# uc.net
KiCad netlist of a schematic drawn in Altium Designer
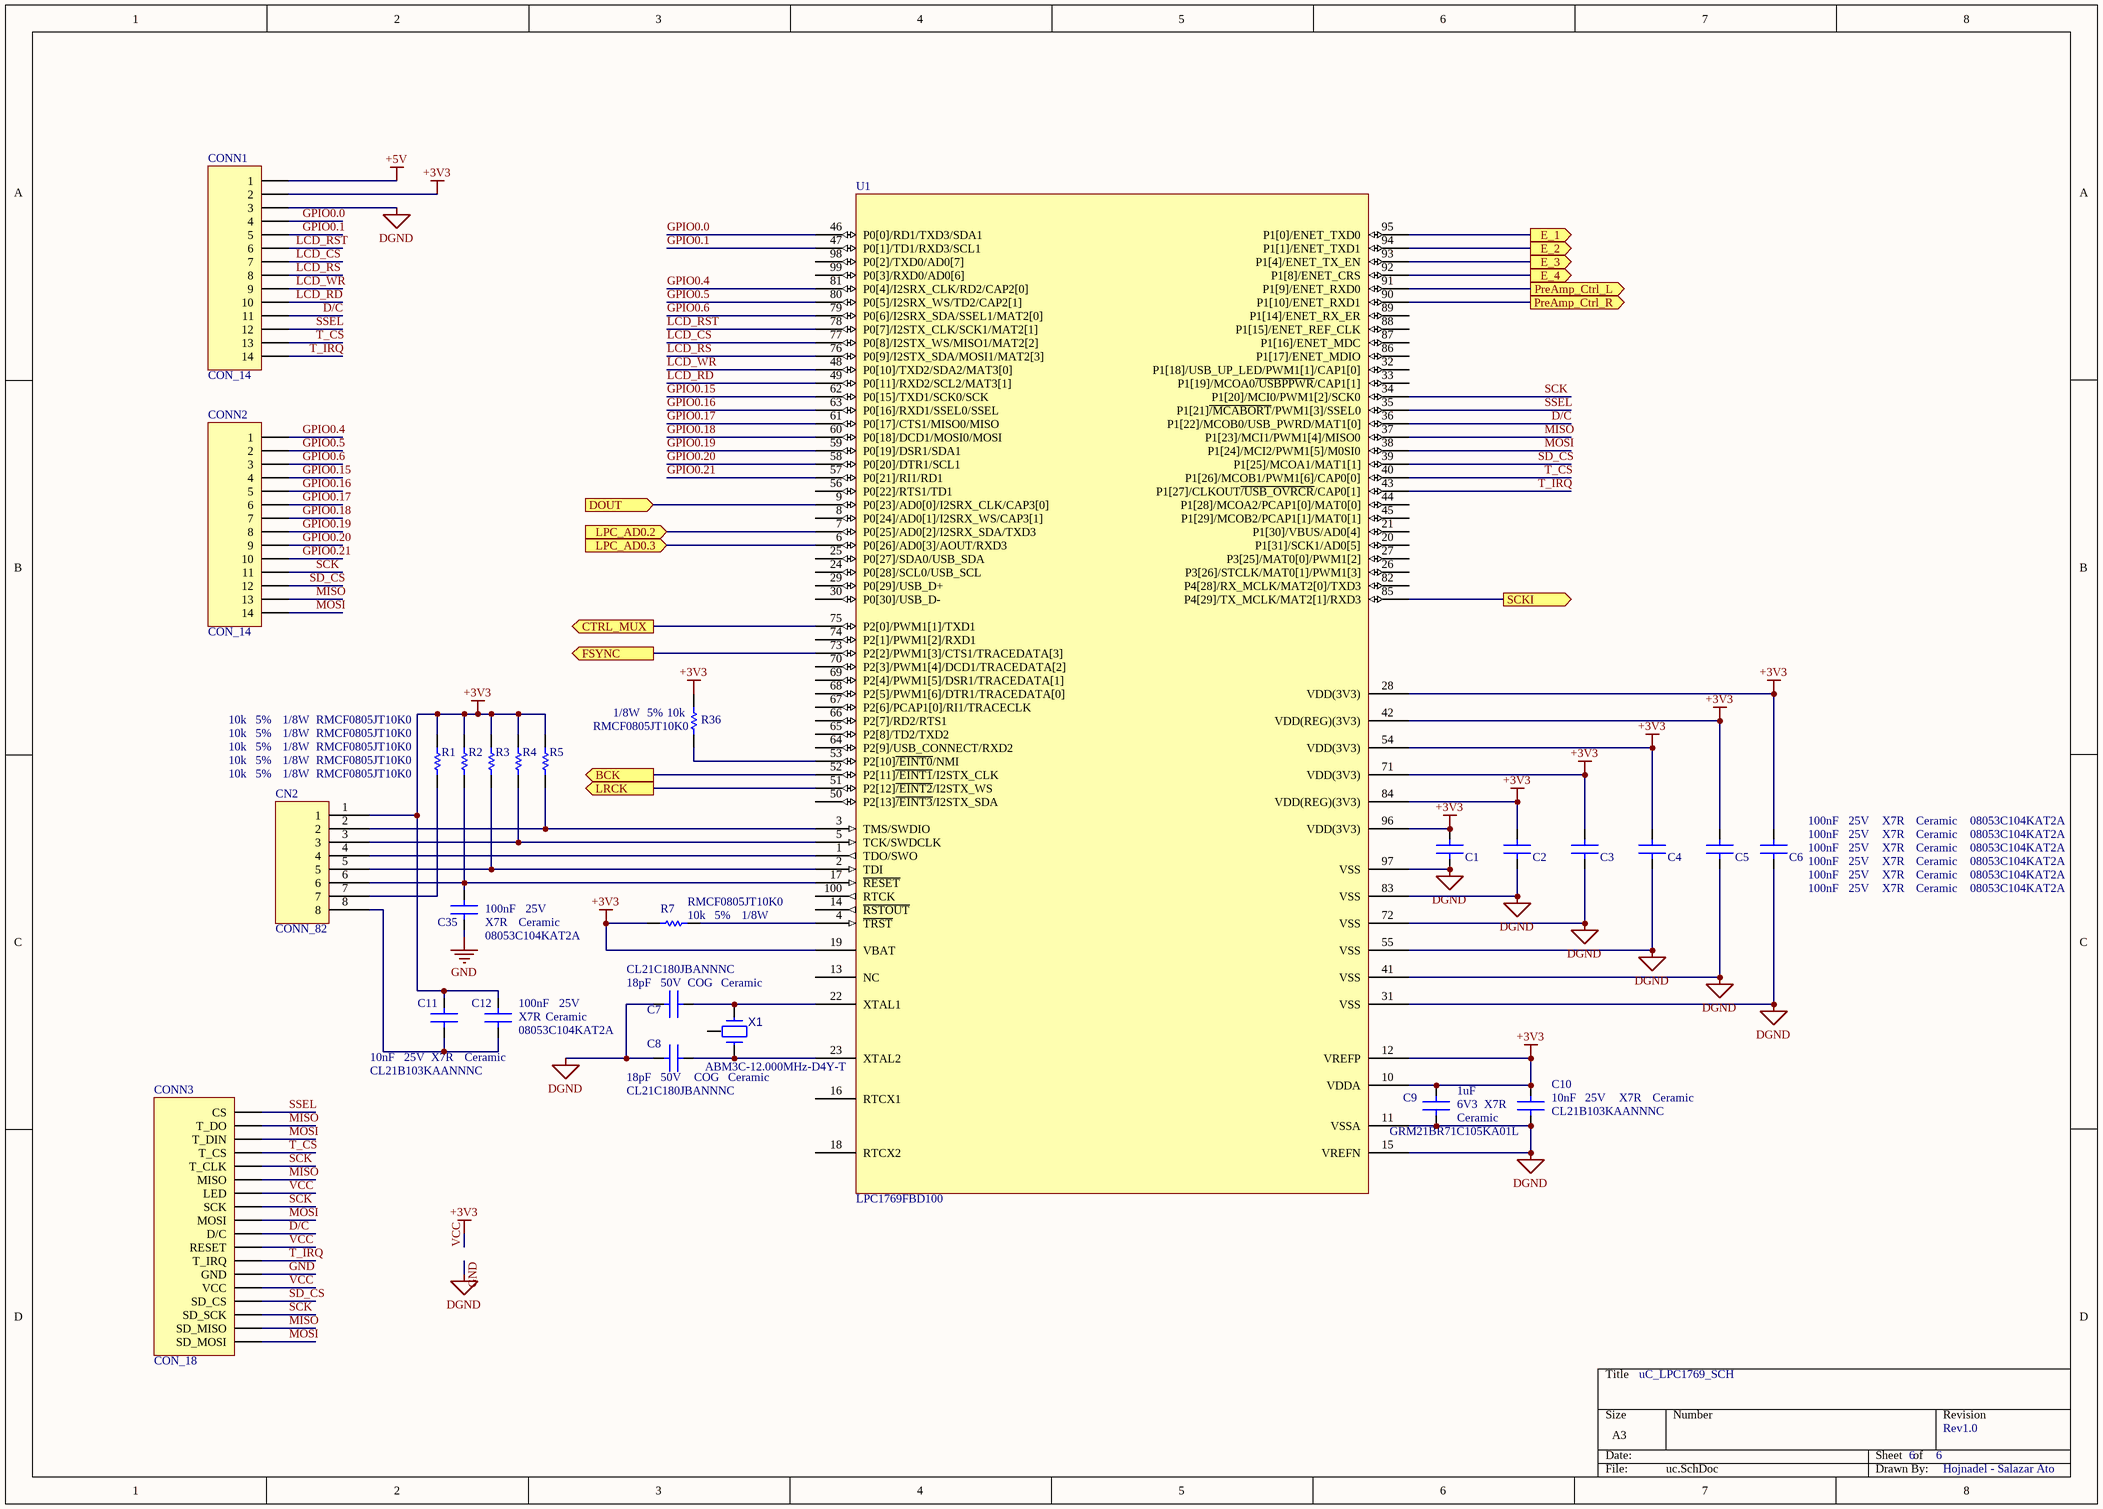
[diagram p0: uc.SchDoc]

(export (version "E")
  (design (tool "Eeschema 10.0.6"))
  (components
    (comp (ref "C1")
      (value "100nF 25V X7R Ceramic")
      (footprint "C_0805")
      (description "Capacitor")
      (fields
        (field (name "C") "100nF")
        (field (name "V") "25V")
        (field (name "PART NUMBER") "08053C104KAT2A")
        (field (name "TEMP COEF") "X7R")
        (field (name "MATERIAL") "Ceramic")
      )
      (libsource (lib "TDII_Lib_V2") (part "Cap1"))
    )
    (comp (ref "C2")
      (value "100nF 25V X7R Ceramic")
      (footprint "C_0805")
      (description "Capacitor")
      (fields
        (field (name "C") "100nF")
        (field (name "V") "25V")
        (field (name "PART NUMBER") "08053C104KAT2A")
        (field (name "TEMP COEF") "X7R")
        (field (name "MATERIAL") "Ceramic")
      )
      (libsource (lib "TDII_Lib_V2") (part "Cap1"))
    )
    (comp (ref "C3")
      (value "100nF 25V X7R Ceramic")
      (footprint "C_0805")
      (description "Capacitor")
      (fields
        (field (name "C") "100nF")
        (field (name "V") "25V")
        (field (name "PART NUMBER") "08053C104KAT2A")
        (field (name "TEMP COEF") "X7R")
        (field (name "MATERIAL") "Ceramic")
      )
      (libsource (lib "TDII_Lib_V2") (part "Cap1"))
    )
    (comp (ref "C4")
      (value "100nF 25V X7R Ceramic")
      (footprint "C_0805")
      (description "Capacitor")
      (fields
        (field (name "C") "100nF")
        (field (name "V") "25V")
        (field (name "PART NUMBER") "08053C104KAT2A")
        (field (name "TEMP COEF") "X7R")
        (field (name "MATERIAL") "Ceramic")
      )
      (libsource (lib "TDII_Lib_V2") (part "Cap1"))
    )
    (comp (ref "C5")
      (value "100nF 25V X7R Ceramic")
      (footprint "C_0805")
      (description "Capacitor")
      (fields
        (field (name "C") "100nF")
        (field (name "V") "25V")
        (field (name "PART NUMBER") "08053C104KAT2A")
        (field (name "TEMP COEF") "X7R")
        (field (name "MATERIAL") "Ceramic")
      )
      (libsource (lib "TDII_Lib_V2") (part "Cap1"))
    )
    (comp (ref "C6")
      (value "100nF 25V X7R Ceramic")
      (footprint "C_0805")
      (description "Capacitor")
      (fields
        (field (name "C") "100nF")
        (field (name "V") "25V")
        (field (name "PART NUMBER") "08053C104KAT2A")
        (field (name "TEMP COEF") "X7R")
        (field (name "MATERIAL") "Ceramic")
      )
      (libsource (lib "TDII_Lib_V2") (part "Cap1"))
    )
    (comp (ref "C7")
      (value "18pF 50V COG Ceramic")
      (footprint "C_0805")
      (description "Capacitor")
      (fields
        (field (name "C") "18pF")
        (field (name "V") "50V")
        (field (name "PART NUMBER") "CL21C180JBANNNC")
        (field (name "TEMP COEF") "COG")
        (field (name "MATERIAL") "Ceramic")
      )
      (libsource (lib "TDII_Lib_V2") (part "Cap1"))
    )
    (comp (ref "C8")
      (value "18pF 50V COG Ceramic")
      (footprint "C_0805")
      (description "Capacitor")
      (fields
        (field (name "C") "18pF")
        (field (name "V") "50V")
        (field (name "PART NUMBER") "CL21C180JBANNNC")
        (field (name "TEMP COEF") "COG")
        (field (name "MATERIAL") "Ceramic")
      )
      (libsource (lib "TDII_Lib_V2") (part "Cap1"))
    )
    (comp (ref "C9")
      (value "1uF 6V3 X7R Ceramic")
      (footprint "C_0805")
      (description "Capacitor")
      (fields
        (field (name "C") "1uF")
        (field (name "V") "6V3")
        (field (name "PART NUMBER") "GRM21BR71C105KA01L")
        (field (name "TEMP COEF") "X7R")
        (field (name "MATERIAL") "Ceramic")
      )
      (libsource (lib "TDII_Lib_V2") (part "Cap1"))
    )
    (comp (ref "C10")
      (value "10nF 25V X7R Ceramic")
      (footprint "C_0805")
      (description "Capacitor")
      (fields
        (field (name "C") "10nF")
        (field (name "V") "25V")
        (field (name "PART NUMBER") "CL21B103KAANNNC")
        (field (name "TEMP COEF") "X7R")
        (field (name "MATERIAL") "Ceramic")
      )
      (libsource (lib "TDII_Lib_V2") (part "Cap1"))
    )
    (comp (ref "C11")
      (value "10nF 25V X7R Ceramic")
      (footprint "C_0805")
      (description "Capacitor")
      (fields
        (field (name "C") "10nF")
        (field (name "V") "25V")
        (field (name "PART NUMBER") "CL21B103KAANNNC")
        (field (name "TEMP COEF") "X7R")
        (field (name "MATERIAL") "Ceramic")
      )
      (libsource (lib "TDII_Lib_V2") (part "Cap1"))
    )
    (comp (ref "C12")
      (value "100nF 25V X7R Ceramic")
      (footprint "C_0805")
      (description "Capacitor")
      (fields
        (field (name "C") "100nF")
        (field (name "V") "25V")
        (field (name "PART NUMBER") "08053C104KAT2A")
        (field (name "TEMP COEF") "X7R")
        (field (name "MATERIAL") "Ceramic")
      )
      (libsource (lib "TDII_Lib_V2") (part "C?"))
    )
    (comp (ref "C35")
      (value "100nF 25V X7R Ceramic")
      (footprint "C_0805")
      (description "Capacitor")
      (fields
        (field (name "C") "100nF")
        (field (name "V") "25V")
        (field (name "TEMP COEF") "X7R")
        (field (name "PART NUMBER") "08053C104KAT2A")
        (field (name "MATERIAL") "Ceramic")
      )
      (libsource (lib "TDII_Lib_V2") (part "C?"))
    )
    (comp (ref "CN2")
      (value "CONN_82")
      (footprint "HDR_M_08P_0.1")
      (libsource (lib "TDII_Lib") (part "CONN_82"))
    )
    (comp (ref "CONN1")
      (value "CON_14")
      (footprint "1x14x2.54 Pin Header TH V")
      (description "CONN TFT 3.5")
      (libsource (lib "TDII_Lib_V2") (part "CON_14"))
    )
    (comp (ref "CONN2")
      (value "CON_14")
      (footprint "1x14x2.54 Pin Header TH V")
      (description "CONN TFT 3.5")
      (libsource (lib "TDII_Lib_V2") (part "CON_14"))
    )
    (comp (ref "CONN3")
      (value "CON_18")
      (footprint "2x9x2.54 Pin Header TH V")
      (description "CON_TFT_2.8")
      (libsource (lib "TDII_Lib_V2") (part "CON_18"))
    )
    (comp (ref "R1")
      (value "10k")
      (footprint "R_0805")
      (description "Resistor")
      (fields
        (field (name "POWER") "1/8W")
        (field (name "PART NUMBER") "RMCF0805JT10K0")
        (field (name "TOLERANCE") "5%")
        (field (name "Comment") "10k 5% 1/8W")
      )
      (libsource (lib "TDII_Lib") (part "Res1"))
    )
    (comp (ref "R2")
      (value "10k")
      (footprint "R_0805")
      (description "Resistor")
      (fields
        (field (name "PART NUMBER") "RMCF0805JT10K0")
        (field (name "TOLERANCE") "5%")
        (field (name "POWER") "1/8W")
        (field (name "Comment") "10k 5% 1/8W")
      )
      (libsource (lib "TDII_Lib") (part "Res1"))
    )
    (comp (ref "R3")
      (value "10k")
      (footprint "R_0805")
      (description "Resistor")
      (fields
        (field (name "POWER") "1/8W")
        (field (name "PART NUMBER") "RMCF0805JT10K0")
        (field (name "TOLERANCE") "5%")
        (field (name "Comment") "10k 5% 1/8W")
      )
      (libsource (lib "TDII_Lib") (part "Res1"))
    )
    (comp (ref "R4")
      (value "10k")
      (footprint "R_0805")
      (description "Resistor")
      (fields
        (field (name "POWER") "1/8W")
        (field (name "PART NUMBER") "RMCF0805JT10K0")
        (field (name "TOLERANCE") "5%")
        (field (name "Comment") "10k 5% 1/8W")
      )
      (libsource (lib "TDII_Lib") (part "Res1"))
    )
    (comp (ref "R5")
      (value "10k")
      (footprint "R_0805")
      (description "Resistor")
      (fields
        (field (name "POWER") "1/8W")
        (field (name "PART NUMBER") "RMCF0805JT10K0")
        (field (name "TOLERANCE") "5%")
        (field (name "Comment") "10k 5% 1/8W")
      )
      (libsource (lib "TDII_Lib") (part "Res1"))
    )
    (comp (ref "R7")
      (value "10k")
      (footprint "R_0805")
      (description "Resistor")
      (fields
        (field (name "POWER") "1/8W")
        (field (name "PART NUMBER") "RMCF0805JT10K0")
        (field (name "TOLERANCE") "5%")
        (field (name "Comment") "10k 5% 1/8W")
      )
      (libsource (lib "TDII_Lib") (part "Res1"))
    )
    (comp (ref "R36")
      (value "10k")
      (footprint "R_0805")
      (description "Resistor")
      (fields
        (field (name "POWER") "1/8W")
        (field (name "PART NUMBER") "RMCF0805JT10K0")
        (field (name "TOLERANCE") "5%")
        (field (name "Comment") "10k 5% 1/8W")
      )
      (libsource (lib "TDII_Lib_V2") (part "Res1"))
    )
    (comp (ref "U1")
      (value "LPC1769FBD100")
      (footprint "LQFP100")
      (description "CPU Cortex M3")
      (libsource (lib "TDII_Lib_V2") (part "LPC1768FBD100"))
    )
    (comp (ref "X1")
      (value "XTAL_HF")
      (footprint "ABMC_XTAL")
      (description "Crystal")
      (fields (field (name "PART NUMBER") "ABM3C-12.000MHz-D4Y-T"))
      (libsource (lib "TDII_Lib_V2") (part "XTAL_HF"))
    )
  )
  (nets
    (net (code "1") (name "+3V3") (class "Default")
      (node (ref "C1") (pin "1") (pinfunction "1_1") (pintype "passive"))
      (node (ref "C10") (pin "1") (pinfunction "1_1") (pintype "passive"))
      (node (ref "C11") (pin "1") (pinfunction "1_1") (pintype "passive"))
      (node (ref "C12") (pin "1") (pinfunction "1_1") (pintype "passive"))
      (node (ref "C2") (pin "1") (pinfunction "1_1") (pintype "passive"))
      (node (ref "C3") (pin "1") (pinfunction "1_1") (pintype "passive"))
      (node (ref "C4") (pin "1") (pinfunction "1_1") (pintype "passive"))
      (node (ref "C5") (pin "1") (pinfunction "1_1") (pintype "passive"))
      (node (ref "C6") (pin "1") (pinfunction "1_1") (pintype "passive"))
      (node (ref "C9") (pin "1") (pinfunction "1_1") (pintype "passive"))
      (node (ref "CN2") (pin "1") (pinfunction "1_1") (pintype "passive"))
      (node (ref "CONN1") (pin "2") (pinfunction "2_2") (pintype "passive"))
      (node (ref "CONN3") (pin "11") (pinfunction "RESET_11") (pintype "passive"))
      (node (ref "CONN3") (pin "14") (pinfunction "VCC_14") (pintype "passive"))
      (node (ref "CONN3") (pin "7") (pinfunction "LED_7") (pintype "passive"))
      (node (ref "R1") (pin "2") (pinfunction "2_2") (pintype "passive"))
      (node (ref "R2") (pin "2") (pinfunction "2_2") (pintype "passive"))
      (node (ref "R3") (pin "2") (pinfunction "2_2") (pintype "passive"))
      (node (ref "R36") (pin "2") (pinfunction "2_2") (pintype "passive"))
      (node (ref "R4") (pin "2") (pinfunction "2_2") (pintype "passive"))
      (node (ref "R5") (pin "2") (pinfunction "2_2") (pintype "passive"))
      (node (ref "R7") (pin "2") (pinfunction "2_2") (pintype "passive"))
      (node (ref "U1") (pin "10") (pinfunction "VDDA_10") (pintype "power_in"))
      (node (ref "U1") (pin "12") (pinfunction "VREFP_12") (pintype "power_in"))
      (node (ref "U1") (pin "19") (pinfunction "VBAT_19") (pintype "power_in"))
      (node (ref "U1") (pin "28") (pinfunction "VDD(3V3)_28") (pintype "power_in"))
      (node (ref "U1") (pin "42") (pinfunction "VDD(REG)(3V3)_42") (pintype "power_in"))
      (node (ref "U1") (pin "54") (pinfunction "VDD(3V3)_54") (pintype "power_in"))
      (node (ref "U1") (pin "71") (pinfunction "VDD(3V3)_71") (pintype "power_in"))
      (node (ref "U1") (pin "84") (pinfunction "VDD(REG)(3V3)_84") (pintype "power_in"))
      (node (ref "U1") (pin "96") (pinfunction "VDD(3V3)_96") (pintype "power_in"))
    )
    (net (code "2") (name "+5V") (class "Default")
      (node (ref "CONN1") (pin "1") (pinfunction "1_1") (pintype "passive"))
    )
    (net (code "3") (name "/BCK") (class "Default")
      (node (ref "U1") (pin "52") (pinfunction "P2[11]~{/EINT1}/I2STX_CLK_52") (pintype "bidirectional"))
    )
    (net (code "4") (name "/CTRL_MUX") (class "Default")
      (node (ref "U1") (pin "75") (pinfunction "P2[0]/PWM1[1]/TXD1_75") (pintype "bidirectional"))
    )
    (net (code "5") (name "/DOUT") (class "Default")
      (node (ref "U1") (pin "9") (pinfunction "P0[23]/AD0[0]/I2SRX_CLK/CAP3[0]_9") (pintype "bidirectional"))
    )
    (net (code "6") (name "/D{slash}C") (class "Default")
      (node (ref "CONN1") (pin "11") (pinfunction "11_11") (pintype "passive"))
      (node (ref "CONN3") (pin "10") (pinfunction "D/C_10") (pintype "passive"))
      (node (ref "U1") (pin "36") (pinfunction "P1[22]/MCOB0/USB_PWRD/MAT1[0]_36") (pintype "bidirectional"))
    )
    (net (code "7") (name "/E_1") (class "Default")
      (node (ref "U1") (pin "95") (pinfunction "P1[0]/ENET_TXD0_95") (pintype "bidirectional"))
    )
    (net (code "8") (name "/E_2") (class "Default")
      (node (ref "U1") (pin "94") (pinfunction "P1[1]/ENET_TXD1_94") (pintype "bidirectional"))
    )
    (net (code "9") (name "/E_3") (class "Default")
      (node (ref "U1") (pin "93") (pinfunction "P1[4]/ENET_TX_EN_93") (pintype "bidirectional"))
    )
    (net (code "10") (name "/E_4") (class "Default")
      (node (ref "U1") (pin "92") (pinfunction "P1[8]/ENET_CRS_92") (pintype "bidirectional"))
    )
    (net (code "11") (name "/FSYNC") (class "Default")
      (node (ref "U1") (pin "73") (pinfunction "P2[2]/PWM1[3]/CTS1/TRACEDATA[3]_73") (pintype "bidirectional"))
    )
    (net (code "12") (name "/GPIO0.0") (class "Default")
      (node (ref "CONN1") (pin "4") (pinfunction "4_4") (pintype "passive"))
      (node (ref "U1") (pin "46") (pinfunction "P0[0]/RD1/TXD3/SDA1_46") (pintype "bidirectional"))
    )
    (net (code "13") (name "/GPIO0.1") (class "Default")
      (node (ref "CONN1") (pin "5") (pinfunction "5_5") (pintype "passive"))
      (node (ref "U1") (pin "47") (pinfunction "P0[1]/TD1/RXD3/SCL1_47") (pintype "bidirectional"))
    )
    (net (code "14") (name "/GPIO0.4") (class "Default")
      (node (ref "CONN2") (pin "1") (pinfunction "1_1") (pintype "passive"))
      (node (ref "U1") (pin "81") (pinfunction "P0[4]/I2SRX_CLK/RD2/CAP2[0]_81") (pintype "bidirectional"))
    )
    (net (code "15") (name "/GPIO0.5") (class "Default")
      (node (ref "CONN2") (pin "2") (pinfunction "2_2") (pintype "passive"))
      (node (ref "U1") (pin "80") (pinfunction "P0[5]/I2SRX_WS/TD2/CAP2[1]_80") (pintype "bidirectional"))
    )
    (net (code "16") (name "/GPIO0.6") (class "Default")
      (node (ref "CONN2") (pin "3") (pinfunction "3_3") (pintype "passive"))
      (node (ref "U1") (pin "79") (pinfunction "P0[6]/I2SRX_SDA/SSEL1/MAT2[0]_79") (pintype "bidirectional"))
    )
    (net (code "17") (name "/GPIO0.15") (class "Default")
      (node (ref "CONN2") (pin "4") (pinfunction "4_4") (pintype "passive"))
      (node (ref "U1") (pin "62") (pinfunction "P0[15]/TXD1/SCK0/SCK_62") (pintype "bidirectional"))
    )
    (net (code "18") (name "/GPIO0.16") (class "Default")
      (node (ref "CONN2") (pin "5") (pinfunction "5_5") (pintype "passive"))
      (node (ref "U1") (pin "63") (pinfunction "P0[16]/RXD1/SSEL0/SSEL_63") (pintype "bidirectional"))
    )
    (net (code "19") (name "/GPIO0.17") (class "Default")
      (node (ref "CONN2") (pin "6") (pinfunction "6_6") (pintype "passive"))
      (node (ref "U1") (pin "61") (pinfunction "P0[17]/CTS1/MISO0/MISO_61") (pintype "bidirectional"))
    )
    (net (code "20") (name "/GPIO0.18") (class "Default")
      (node (ref "CONN2") (pin "7") (pinfunction "7_7") (pintype "passive"))
      (node (ref "U1") (pin "60") (pinfunction "P0[18]/DCD1/MOSI0/MOSI_60") (pintype "bidirectional"))
    )
    (net (code "21") (name "/GPIO0.19") (class "Default")
      (node (ref "CONN2") (pin "8") (pinfunction "8_8") (pintype "passive"))
      (node (ref "U1") (pin "59") (pinfunction "P0[19]/DSR1/SDA1_59") (pintype "bidirectional"))
    )
    (net (code "22") (name "/GPIO0.20") (class "Default")
      (node (ref "CONN2") (pin "9") (pinfunction "9_9") (pintype "passive"))
      (node (ref "U1") (pin "58") (pinfunction "P0[20]/DTR1/SCL1_58") (pintype "bidirectional"))
    )
    (net (code "23") (name "/GPIO0.21") (class "Default")
      (node (ref "CONN2") (pin "10") (pinfunction "10_10") (pintype "passive"))
      (node (ref "U1") (pin "57") (pinfunction "P0[21]/RI1/RD1_57") (pintype "bidirectional"))
    )
    (net (code "24") (name "/LCD_CS") (class "Default")
      (node (ref "CONN1") (pin "7") (pinfunction "7_7") (pintype "passive"))
      (node (ref "U1") (pin "77") (pinfunction "P0[8]/I2STX_WS/MISO1/MAT2[2]_77") (pintype "bidirectional"))
    )
    (net (code "25") (name "/LCD_RD") (class "Default")
      (node (ref "CONN1") (pin "10") (pinfunction "10_10") (pintype "passive"))
      (node (ref "U1") (pin "49") (pinfunction "P0[11]/RXD2/SCL2/MAT3[1]_49") (pintype "bidirectional"))
    )
    (net (code "26") (name "/LCD_RS") (class "Default")
      (node (ref "CONN1") (pin "8") (pinfunction "8_8") (pintype "passive"))
      (node (ref "U1") (pin "76") (pinfunction "P0[9]/I2STX_SDA/MOSI1/MAT2[3]_76") (pintype "bidirectional"))
    )
    (net (code "27") (name "/LCD_RST") (class "Default")
      (node (ref "CONN1") (pin "6") (pinfunction "6_6") (pintype "passive"))
      (node (ref "U1") (pin "78") (pinfunction "P0[7]/I2STX_CLK/SCK1/MAT2[1]_78") (pintype "bidirectional"))
    )
    (net (code "28") (name "/LCD_WR") (class "Default")
      (node (ref "CONN1") (pin "9") (pinfunction "9_9") (pintype "passive"))
      (node (ref "U1") (pin "48") (pinfunction "P0[10]/TXD2/SDA2/MAT3[0]_48") (pintype "bidirectional"))
    )
    (net (code "29") (name "/LPC_AD0.2") (class "Default")
      (node (ref "U1") (pin "7") (pinfunction "P0[25]/AD0[2]/I2SRX_SDA/TXD3_7") (pintype "bidirectional"))
    )
    (net (code "30") (name "/LPC_AD0.3") (class "Default")
      (node (ref "U1") (pin "6") (pinfunction "P0[26]/AD0[3]/AOUT/RXD3_6") (pintype "bidirectional"))
    )
    (net (code "31") (name "/LRCK") (class "Default")
      (node (ref "U1") (pin "51") (pinfunction "P2[12]~{/EINT2}/I2STX_WS_51") (pintype "bidirectional"))
    )
    (net (code "32") (name "/MISO") (class "Default")
      (node (ref "CONN2") (pin "13") (pinfunction "13_13") (pintype "passive"))
      (node (ref "CONN3") (pin "17") (pinfunction "SD_MISO_17") (pintype "passive"))
      (node (ref "CONN3") (pin "2") (pinfunction "T_DO_2") (pintype "passive"))
      (node (ref "CONN3") (pin "6") (pinfunction "MISO_6") (pintype "passive"))
      (node (ref "U1") (pin "37") (pinfunction "P1[23]/MCI1/PWM1[4]/MISO0_37") (pintype "bidirectional"))
    )
    (net (code "33") (name "/MOSI") (class "Default")
      (node (ref "CONN2") (pin "14") (pinfunction "14_14") (pintype "passive"))
      (node (ref "CONN3") (pin "18") (pinfunction "SD_MOSI_18") (pintype "passive"))
      (node (ref "CONN3") (pin "3") (pinfunction "T_DIN_3") (pintype "passive"))
      (node (ref "CONN3") (pin "9") (pinfunction "MOSI_9") (pintype "passive"))
      (node (ref "U1") (pin "38") (pinfunction "P1[24]/MCI2/PWM1[5]/M0SI0_38") (pintype "bidirectional"))
    )
    (net (code "34") (name "/PreAmp_Ctrl_L") (class "Default")
      (node (ref "U1") (pin "91") (pinfunction "P1[9]/ENET_RXD0_91") (pintype "bidirectional"))
    )
    (net (code "35") (name "/PreAmp_Ctrl_R") (class "Default")
      (node (ref "U1") (pin "90") (pinfunction "P1[10]/ENET_RXD1_90") (pintype "bidirectional"))
    )
    (net (code "36") (name "/SCK") (class "Default")
      (node (ref "CONN2") (pin "11") (pinfunction "11_11") (pintype "passive"))
      (node (ref "CONN3") (pin "16") (pinfunction "SD_SCK_16") (pintype "passive"))
      (node (ref "CONN3") (pin "5") (pinfunction "T_CLK_5") (pintype "passive"))
      (node (ref "CONN3") (pin "8") (pinfunction "SCK_8") (pintype "passive"))
      (node (ref "U1") (pin "34") (pinfunction "P1[20]/MCI0/PWM1[2]/SCK0_34") (pintype "bidirectional"))
    )
    (net (code "37") (name "/SCKI") (class "Default")
      (node (ref "U1") (pin "85") (pinfunction "P4[29]/TX_MCLK/MAT2[1]/RXD3_85") (pintype "bidirectional"))
    )
    (net (code "38") (name "/SD_CS") (class "Default")
      (node (ref "CONN2") (pin "12") (pinfunction "12_12") (pintype "passive"))
      (node (ref "CONN3") (pin "15") (pinfunction "SD_CS_15") (pintype "passive"))
      (node (ref "U1") (pin "39") (pinfunction "P1[25]/MCOA1/MAT1[1]_39") (pintype "bidirectional"))
    )
    (net (code "39") (name "/SSEL") (class "Default")
      (node (ref "CONN1") (pin "12") (pinfunction "12_12") (pintype "passive"))
      (node (ref "CONN3") (pin "1") (pinfunction "CS_1") (pintype "passive"))
      (node (ref "U1") (pin "35") (pinfunction "P1[21]~{/MCABORT}/PWM1[3]/SSEL0_35") (pintype "bidirectional"))
    )
    (net (code "40") (name "/T_CS") (class "Default")
      (node (ref "CONN1") (pin "13") (pinfunction "13_13") (pintype "passive"))
      (node (ref "CONN3") (pin "4") (pinfunction "T_CS_4") (pintype "passive"))
      (node (ref "U1") (pin "40") (pinfunction "P1[26]/MCOB1/PWM1[6]/CAP0[0]_40") (pintype "bidirectional"))
    )
    (net (code "41") (name "/T_IRQ") (class "Default")
      (node (ref "CONN1") (pin "14") (pinfunction "14_14") (pintype "passive"))
      (node (ref "CONN3") (pin "12") (pinfunction "T_IRQ_12") (pintype "passive"))
      (node (ref "U1") (pin "43") (pinfunction "P1[27]/CLKOUT~{/USB_OVRCR}/CAP0[1]_43") (pintype "bidirectional"))
    )
    (net (code "42") (name "DGND") (class "Default")
      (node (ref "C1") (pin "2") (pinfunction "2_2") (pintype "passive"))
      (node (ref "C10") (pin "2") (pinfunction "2_2") (pintype "passive"))
      (node (ref "C2") (pin "2") (pinfunction "2_2") (pintype "passive"))
      (node (ref "C3") (pin "2") (pinfunction "2_2") (pintype "passive"))
      (node (ref "C35") (pin "2") (pinfunction "2_2") (pintype "passive"))
      (node (ref "C4") (pin "2") (pinfunction "2_2") (pintype "passive"))
      (node (ref "C5") (pin "2") (pinfunction "2_2") (pintype "passive"))
      (node (ref "C6") (pin "2") (pinfunction "2_2") (pintype "passive"))
      (node (ref "C7") (pin "1") (pinfunction "1_1") (pintype "passive"))
      (node (ref "C8") (pin "1") (pinfunction "1_1") (pintype "passive"))
      (node (ref "C9") (pin "2") (pinfunction "2_2") (pintype "passive"))
      (node (ref "CONN1") (pin "3") (pinfunction "3_3") (pintype "passive"))
      (node (ref "CONN3") (pin "13") (pinfunction "GND_13") (pintype "passive"))
      (node (ref "U1") (pin "11") (pinfunction "VSSA_11") (pintype "power_in"))
      (node (ref "U1") (pin "15") (pinfunction "VREFN_15") (pintype "power_in"))
      (node (ref "U1") (pin "31") (pinfunction "VSS_31") (pintype "power_in"))
      (node (ref "U1") (pin "41") (pinfunction "VSS_41") (pintype "power_in"))
      (node (ref "U1") (pin "55") (pinfunction "VSS_55") (pintype "power_in"))
      (node (ref "U1") (pin "72") (pinfunction "VSS_72") (pintype "power_in"))
      (node (ref "U1") (pin "83") (pinfunction "VSS_83") (pintype "power_in"))
      (node (ref "U1") (pin "97") (pinfunction "VSS_97") (pintype "power_in"))
    )
    (net (code "43") (name "Net-(C11-Pad2)") (class "Default")
      (node (ref "C11") (pin "2") (pinfunction "2_2") (pintype "passive"))
      (node (ref "C12") (pin "2") (pinfunction "2_2") (pintype "passive"))
      (node (ref "CN2") (pin "8") (pinfunction "8_8") (pintype "passive"))
    )
    (net (code "44") (name "Net-(CN2-Pad7)") (class "Default")
      (node (ref "CN2") (pin "7") (pinfunction "7_7") (pintype "passive"))
      (node (ref "R1") (pin "1") (pinfunction "1_1") (pintype "passive"))
    )
    (net (code "45") (name "Net-(U1-P2[10]~{{slash}EINT0}{slash}NMI)") (class "Default")
      (node (ref "R36") (pin "1") (pinfunction "1_1") (pintype "passive"))
      (node (ref "U1") (pin "53") (pinfunction "P2[10]~{/EINT0}/NMI_53") (pintype "bidirectional"))
    )
    (net (code "46") (name "Net-(U1-TCK{slash}SWDCLK)") (class "Default")
      (node (ref "CN2") (pin "3") (pinfunction "3_3") (pintype "passive"))
      (node (ref "R4") (pin "1") (pinfunction "1_1") (pintype "passive"))
      (node (ref "U1") (pin "5") (pinfunction "TCK/SWDCLK_5") (pintype "input"))
    )
    (net (code "47") (name "Net-(U1-TDI)") (class "Default")
      (node (ref "CN2") (pin "5") (pinfunction "5_5") (pintype "passive"))
      (node (ref "R3") (pin "1") (pinfunction "1_1") (pintype "passive"))
      (node (ref "U1") (pin "2") (pinfunction "TDI_2") (pintype "input"))
    )
    (net (code "48") (name "Net-(U1-TDO{slash}SWO)") (class "Default")
      (node (ref "CN2") (pin "4") (pinfunction "4_4") (pintype "passive"))
      (node (ref "U1") (pin "1") (pinfunction "TDO/SWO_1") (pintype "output"))
    )
    (net (code "49") (name "Net-(U1-TMS{slash}SWDIO)") (class "Default")
      (node (ref "CN2") (pin "2") (pinfunction "2_2") (pintype "passive"))
      (node (ref "R5") (pin "1") (pinfunction "1_1") (pintype "passive"))
      (node (ref "U1") (pin "3") (pinfunction "TMS/SWDIO_3") (pintype "input"))
    )
    (net (code "50") (name "Net-(U1-XTAL1)") (class "Default")
      (node (ref "C7") (pin "2") (pinfunction "2_2") (pintype "passive"))
      (node (ref "U1") (pin "22") (pinfunction "XTAL1_22") (pintype "passive"))
      (node (ref "X1") (pin "1") (pinfunction "1_1") (pintype "passive"))
    )
    (net (code "51") (name "Net-(U1-XTAL2)") (class "Default")
      (node (ref "C8") (pin "2") (pinfunction "2_2") (pintype "passive"))
      (node (ref "U1") (pin "23") (pinfunction "XTAL2_23") (pintype "passive"))
      (node (ref "X1") (pin "3") (pinfunction "3_3") (pintype "passive"))
    )
    (net (code "52") (name "Net-(U1-~{RESET})") (class "Default")
      (node (ref "C35") (pin "1") (pinfunction "1_1") (pintype "passive"))
      (node (ref "CN2") (pin "6") (pinfunction "6_6") (pintype "passive"))
      (node (ref "R2") (pin "1") (pinfunction "1_1") (pintype "passive"))
      (node (ref "U1") (pin "17") (pinfunction "~{RESET}_17") (pintype "input"))
    )
    (net (code "53") (name "Net-(U1-~{TRST})") (class "Default")
      (node (ref "R7") (pin "1") (pinfunction "1_1") (pintype "passive"))
      (node (ref "U1") (pin "4") (pinfunction "~{TRST}_4") (pintype "input"))
    )
    (net (code "54") (name "Net-(X1-GND)") (class "Default")
      (node (ref "X1") (pin "2") (pinfunction "GND_2") (pintype "passive"))
      (node (ref "X1") (pin "4") (pinfunction "4_4") (pintype "passive"))
    )
    (net (code "55") (name "unconnected-(U1-NC-Pad13)") (class "Default")
      (node (ref "U1") (pin "13") (pinfunction "NC_13") (pintype "passive"))
    )
    (net (code "56") (name "unconnected-(U1-P0[2]{slash}TXD0{slash}AD0[7]-Pad98)") (class "Default")
      (node (ref "U1") (pin "98") (pinfunction "P0[2]/TXD0/AD0[7]_98") (pintype "bidirectional"))
    )
    (net (code "57") (name "unconnected-(U1-P0[3]{slash}RXD0{slash}AD0[6]-Pad99)") (class "Default")
      (node (ref "U1") (pin "99") (pinfunction "P0[3]/RXD0/AD0[6]_99") (pintype "bidirectional"))
    )
    (net (code "58") (name "unconnected-(U1-P0[22]{slash}RTS1{slash}TD1-Pad56)") (class "Default")
      (node (ref "U1") (pin "56") (pinfunction "P0[22]/RTS1/TD1_56") (pintype "bidirectional"))
    )
    (net (code "59") (name "unconnected-(U1-P0[24]{slash}AD0[1]{slash}I2SRX_WS{slash}CAP3[1]-Pad8)") (class "Default")
      (node (ref "U1") (pin "8") (pinfunction "P0[24]/AD0[1]/I2SRX_WS/CAP3[1]_8") (pintype "bidirectional"))
    )
    (net (code "60") (name "unconnected-(U1-P0[27]{slash}SDA0{slash}USB_SDA-Pad25)") (class "Default")
      (node (ref "U1") (pin "25") (pinfunction "P0[27]/SDA0/USB_SDA_25") (pintype "bidirectional"))
    )
    (net (code "61") (name "unconnected-(U1-P0[28]{slash}SCL0{slash}USB_SCL-Pad24)") (class "Default")
      (node (ref "U1") (pin "24") (pinfunction "P0[28]/SCL0/USB_SCL_24") (pintype "bidirectional"))
    )
    (net (code "62") (name "unconnected-(U1-P0[29]{slash}USB_D+-Pad29)") (class "Default")
      (node (ref "U1") (pin "29") (pinfunction "P0[29]/USB_D+_29") (pintype "bidirectional"))
    )
    (net (code "63") (name "unconnected-(U1-P0[30]{slash}USB_D--Pad30)") (class "Default")
      (node (ref "U1") (pin "30") (pinfunction "P0[30]/USB_D-_30") (pintype "bidirectional"))
    )
    (net (code "64") (name "unconnected-(U1-P1[14]{slash}ENET_RX_ER-Pad89)") (class "Default")
      (node (ref "U1") (pin "89") (pinfunction "P1[14]/ENET_RX_ER_89") (pintype "bidirectional"))
    )
    (net (code "65") (name "unconnected-(U1-P1[15]{slash}ENET_REF_CLK-Pad88)") (class "Default")
      (node (ref "U1") (pin "88") (pinfunction "P1[15]/ENET_REF_CLK_88") (pintype "bidirectional"))
    )
    (net (code "66") (name "unconnected-(U1-P1[16]{slash}ENET_MDC-Pad87)") (class "Default")
      (node (ref "U1") (pin "87") (pinfunction "P1[16]/ENET_MDC_87") (pintype "bidirectional"))
    )
    (net (code "67") (name "unconnected-(U1-P1[17]{slash}ENET_MDIO-Pad86)") (class "Default")
      (node (ref "U1") (pin "86") (pinfunction "P1[17]/ENET_MDIO_86") (pintype "bidirectional"))
    )
    (net (code "68") (name "unconnected-(U1-P1[18]{slash}USB_UP_LED{slash}PWM1[1]{slash}CAP1[0]-Pad32)") (class "Default")
      (node (ref "U1") (pin "32") (pinfunction "P1[18]/USB_UP_LED/PWM1[1]/CAP1[0]_32") (pintype "bidirectional"))
    )
    (net (code "69") (name "unconnected-(U1-P1[19]{slash}MCOA0~{{slash}USBPPWR}{slash}CAP1[1]-Pad33)") (class "Default")
      (node (ref "U1") (pin "33") (pinfunction "P1[19]/MCOA0~{/USBPPWR}/CAP1[1]_33") (pintype "bidirectional"))
    )
    (net (code "70") (name "unconnected-(U1-P1[28]{slash}MCOA2{slash}PCAP1[0]{slash}MAT0[0]-Pad44)") (class "Default")
      (node (ref "U1") (pin "44") (pinfunction "P1[28]/MCOA2/PCAP1[0]/MAT0[0]_44") (pintype "bidirectional"))
    )
    (net (code "71") (name "unconnected-(U1-P1[29]{slash}MCOB2{slash}PCAP1[1]{slash}MAT0[1]-Pad45)") (class "Default")
      (node (ref "U1") (pin "45") (pinfunction "P1[29]/MCOB2/PCAP1[1]/MAT0[1]_45") (pintype "bidirectional"))
    )
    (net (code "72") (name "unconnected-(U1-P1[30]{slash}VBUS{slash}AD0[4]-Pad21)") (class "Default")
      (node (ref "U1") (pin "21") (pinfunction "P1[30]/VBUS/AD0[4]_21") (pintype "bidirectional"))
    )
    (net (code "73") (name "unconnected-(U1-P1[31]{slash}SCK1{slash}AD0[5]-Pad20)") (class "Default")
      (node (ref "U1") (pin "20") (pinfunction "P1[31]/SCK1/AD0[5]_20") (pintype "bidirectional"))
    )
    (net (code "74") (name "unconnected-(U1-P2[1]{slash}PWM1[2]{slash}RXD1-Pad74)") (class "Default")
      (node (ref "U1") (pin "74") (pinfunction "P2[1]/PWM1[2]/RXD1_74") (pintype "bidirectional"))
    )
    (net (code "75") (name "unconnected-(U1-P2[3]{slash}PWM1[4]{slash}DCD1{slash}TRACEDATA[2]-Pad70)") (class "Default")
      (node (ref "U1") (pin "70") (pinfunction "P2[3]/PWM1[4]/DCD1/TRACEDATA[2]_70") (pintype "bidirectional"))
    )
    (net (code "76") (name "unconnected-(U1-P2[4]{slash}PWM1[5]{slash}DSR1{slash}TRACEDATA[1]-Pad69)") (class "Default")
      (node (ref "U1") (pin "69") (pinfunction "P2[4]/PWM1[5]/DSR1/TRACEDATA[1]_69") (pintype "bidirectional"))
    )
    (net (code "77") (name "unconnected-(U1-P2[5]{slash}PWM1[6]{slash}DTR1{slash}TRACEDATA[0]-Pad68)") (class "Default")
      (node (ref "U1") (pin "68") (pinfunction "P2[5]/PWM1[6]/DTR1/TRACEDATA[0]_68") (pintype "bidirectional"))
    )
    (net (code "78") (name "unconnected-(U1-P2[6]{slash}PCAP1[0]{slash}RI1{slash}TRACECLK-Pad67)") (class "Default")
      (node (ref "U1") (pin "67") (pinfunction "P2[6]/PCAP1[0]/RI1/TRACECLK_67") (pintype "bidirectional"))
    )
    (net (code "79") (name "unconnected-(U1-P2[7]{slash}RD2{slash}RTS1-Pad66)") (class "Default")
      (node (ref "U1") (pin "66") (pinfunction "P2[7]/RD2/RTS1_66") (pintype "bidirectional"))
    )
    (net (code "80") (name "unconnected-(U1-P2[8]{slash}TD2{slash}TXD2-Pad65)") (class "Default")
      (node (ref "U1") (pin "65") (pinfunction "P2[8]/TD2/TXD2_65") (pintype "bidirectional"))
    )
    (net (code "81") (name "unconnected-(U1-P2[9]{slash}USB_CONNECT{slash}RXD2-Pad64)") (class "Default")
      (node (ref "U1") (pin "64") (pinfunction "P2[9]/USB_CONNECT/RXD2_64") (pintype "bidirectional"))
    )
    (net (code "82") (name "unconnected-(U1-P2[13]~{{slash}EINT3}{slash}I2STX_SDA-Pad50)") (class "Default")
      (node (ref "U1") (pin "50") (pinfunction "P2[13]~{/EINT3}/I2STX_SDA_50") (pintype "bidirectional"))
    )
    (net (code "83") (name "unconnected-(U1-P3[25]{slash}MAT0[0]{slash}PWM1[2]-Pad27)") (class "Default")
      (node (ref "U1") (pin "27") (pinfunction "P3[25]/MAT0[0]/PWM1[2]_27") (pintype "bidirectional"))
    )
    (net (code "84") (name "unconnected-(U1-P3[26]{slash}STCLK{slash}MAT0[1]{slash}PWM1[3]-Pad26)") (class "Default")
      (node (ref "U1") (pin "26") (pinfunction "P3[26]/STCLK/MAT0[1]/PWM1[3]_26") (pintype "bidirectional"))
    )
    (net (code "85") (name "unconnected-(U1-P4[28]{slash}RX_MCLK{slash}MAT2[0]{slash}TXD3-Pad82)") (class "Default")
      (node (ref "U1") (pin "82") (pinfunction "P4[28]/RX_MCLK/MAT2[0]/TXD3_82") (pintype "bidirectional"))
    )
    (net (code "86") (name "unconnected-(U1-RTCK-Pad100)") (class "Default")
      (node (ref "U1") (pin "100") (pinfunction "RTCK_100") (pintype "output"))
    )
    (net (code "87") (name "unconnected-(U1-RTCX1-Pad16)") (class "Default")
      (node (ref "U1") (pin "16") (pinfunction "RTCX1_16") (pintype "passive"))
    )
    (net (code "88") (name "unconnected-(U1-RTCX2-Pad18)") (class "Default")
      (node (ref "U1") (pin "18") (pinfunction "RTCX2_18") (pintype "passive"))
    )
    (net (code "89") (name "unconnected-(U1-~{RSTOUT}-Pad14)") (class "Default")
      (node (ref "U1") (pin "14") (pinfunction "~{RSTOUT}_14") (pintype "output"))
    )
  )
)
